# PowerSystem.net
KiCad netlist of a schematic drawn in Altium Designer
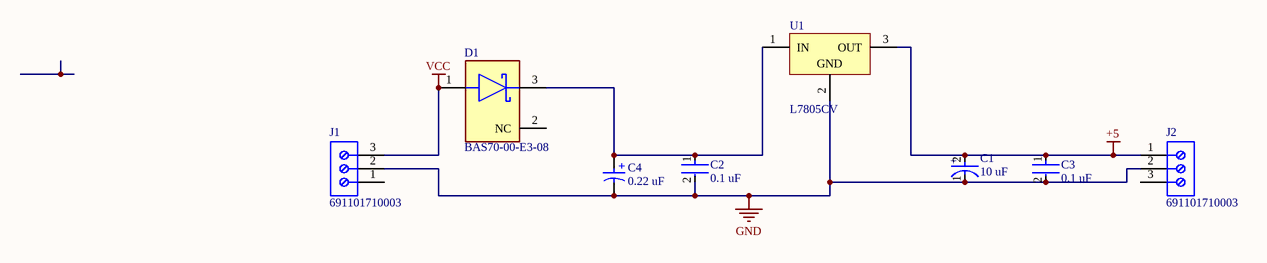
[diagram p0: PowerSystem.SchDoc]

(export (version "E")
  (design (tool "Eeschema 10.0.6"))
  (components
    (comp (ref "C1")
      (value "10 uF")
      (footprint "FP-RAD-TH-D_5_0_5-L_11_1-MFG")
      (description "Aluminum Electrolytic Capacitors (Radial Lead Type) 10uF ±20% 50V")
      (fields (field (name "TOLERANCE") "20%") (field (name "VOLTAGE") "50V"))
      (libsource (lib "Altium Content Vault") (part "a00bbbee19879c290e62620ae7e47b1"))
    )
    (comp (ref "C2")
      (value "0.1 uF")
      (footprint "FP-RDE0P1-MFG")
      (description "Ceramic Capacitor 100nF ±10% 25V X7R Radial")
      (fields (field (name "TOLERANCE") "10%"))
      (libsource (lib "Altium Content Vault") (part "b4654b650e69147ec39a6b967a45e02"))
    )
    (comp (ref "C3")
      (value "0.1 uF")
      (footprint "FP-RDE0P1-MFG")
      (description "Ceramic Capacitor 100nF ±10% 25V X7R Radial")
      (fields (field (name "TOLERANCE") "10%"))
      (libsource (lib "Altium Content Vault") (part "b4654b650e69147ec39a6b967a45e02"))
    )
    (comp (ref "C4")
      (value "0.22 uF")
      (footprint "WCAP-ATG8_D5H11")
      (description "860010772002 WCAP-ATG8 Aluminum Electrolytic Capacitors")
      (fields (field (name "TOLERANCE") "20%"))
      (libsource (lib "Altium Content Vault") (part "Capacitor_Polarized"))
    )
    (comp (ref "D1")
      (value "BAS70-00-E3-08")
      (footprint "FP-6_541-5014_01-4-MFG")
      (description "Diode Small Signal Schottky 70V 0.2A 3-Pin SOT-23 T/R")
      (fields (field (name "MANUFACTURER") "Vishay"))
      (libsource (lib "Altium Content Vault") (part "1b5d8b3549dd4c20f048bc998ce9ad4"))
    )
    (comp (ref "J1")
      (value "691101710003")
      (footprint "691101710003")
      (fields (field (name "VOLTAGE") "250V"))
      (libsource (lib "Altium Content Vault") (part "TBL - 1R - 03P - Screw"))
    )
    (comp (ref "J2")
      (value "691101710003")
      (footprint "691101710003")
      (fields (field (name "VOLTAGE") "250V"))
      (libsource (lib "Altium Content Vault") (part "TBL - 1R - 03P - Screw"))
    )
    (comp (ref "U1")
      (value "L7805CV")
      (footprint "TO220")
      (description "Positive Voltage Regulator, 5V, 3-Pin TO-220")
      (libsource (lib "Altium Content Vault") (part "PM-REG-L4940-SIL3"))
    )
  )
  (nets
    (net (code "1") (name "+5") (class "Default")
      (node (ref "C1") (pin "2") (pinfunction "A_2") (pintype "passive"))
      (node (ref "C3") (pin "1") (pinfunction "1_1") (pintype "passive"))
      (node (ref "J2") (pin "1") (pinfunction "1_1") (pintype "passive"))
      (node (ref "U1") (pin "3") (pinfunction "OUT_3") (pintype "power_in"))
    )
    (net (code "2") (name "GND") (class "Default")
      (node (ref "C1") (pin "1") (pinfunction "C_1") (pintype "passive"))
      (node (ref "C2") (pin "2") (pinfunction "2_2") (pintype "passive"))
      (node (ref "C3") (pin "2") (pinfunction "2_2") (pintype "passive"))
      (node (ref "C4") (pin "2") (pinfunction "N_2") (pintype "passive"))
      (node (ref "J1") (pin "2") (pinfunction "2_2") (pintype "passive"))
      (node (ref "J2") (pin "2") (pinfunction "2_2") (pintype "passive"))
      (node (ref "U1") (pin "2") (pinfunction "GND_2") (pintype "power_in"))
    )
    (net (code "3") (name "Net-(C4-P)") (class "Default")
      (node (ref "C2") (pin "1") (pinfunction "1_1") (pintype "passive"))
      (node (ref "C4") (pin "1") (pinfunction "P_1") (pintype "passive"))
      (node (ref "D1") (pin "3") (pinfunction "C_3") (pintype "passive"))
      (node (ref "U1") (pin "1") (pinfunction "IN_1") (pintype "power_in"))
    )
    (net (code "4") (name "VCC") (class "Default")
      (node (ref "D1") (pin "1") (pinfunction "A_1") (pintype "passive"))
      (node (ref "J1") (pin "3") (pinfunction "3_3") (pintype "passive"))
    )
    (net (code "5") (name "unconnected-(D1-NC-Pad2)") (class "Default")
      (node (ref "D1") (pin "2") (pinfunction "NC_2") (pintype "passive"))
    )
    (net (code "6") (name "unconnected-(J1-Pad1)") (class "Default")
      (node (ref "J1") (pin "1") (pinfunction "1_1") (pintype "passive"))
    )
    (net (code "7") (name "unconnected-(J2-Pad3)") (class "Default")
      (node (ref "J2") (pin "3") (pinfunction "3_3") (pintype "passive"))
    )
  )
)
